# Volume_Button_LED_5.net
KiCad netlist of a schematic drawn in EAGLE
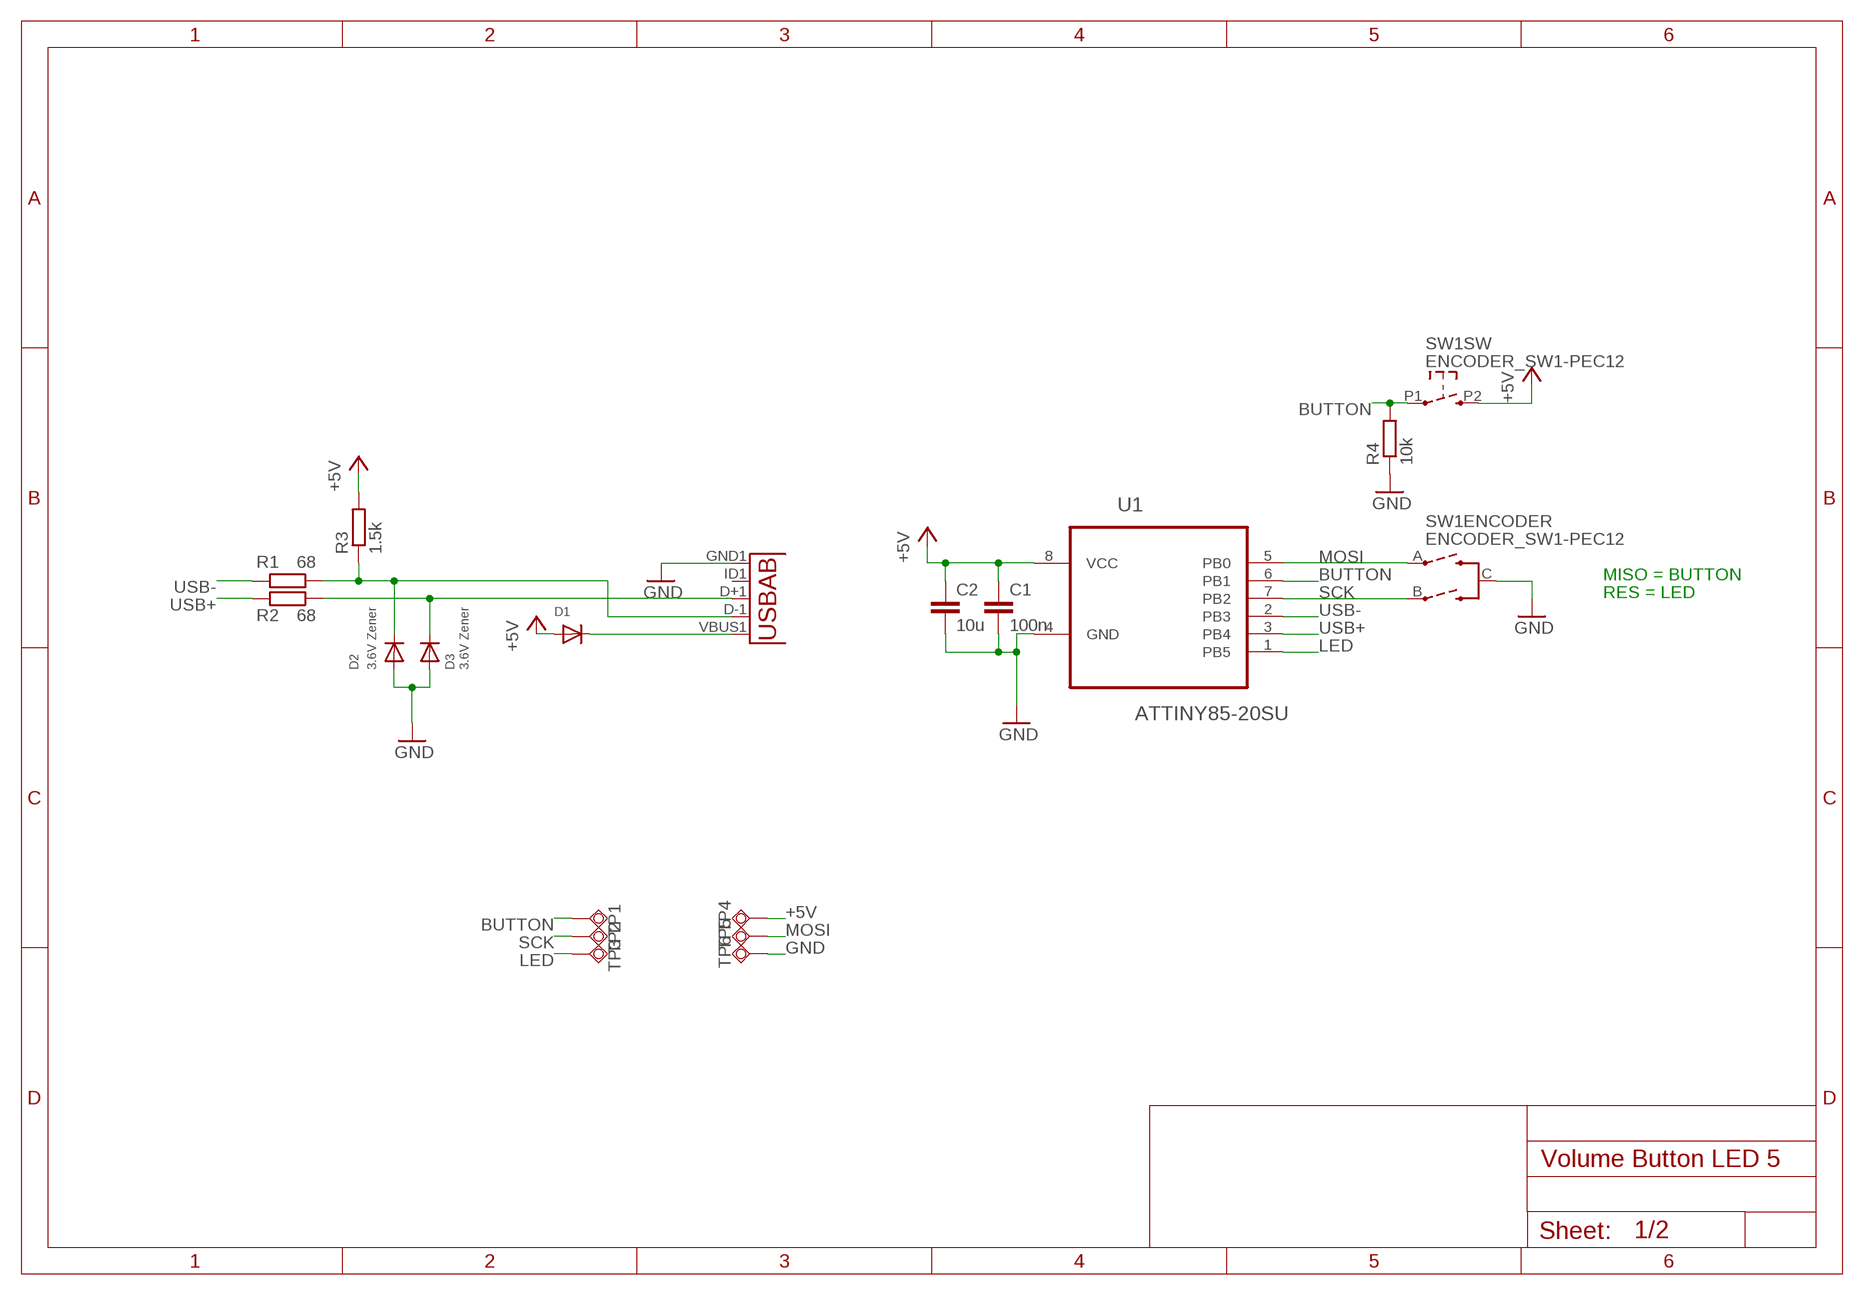
[diagram p0: schematic, sheet 1]
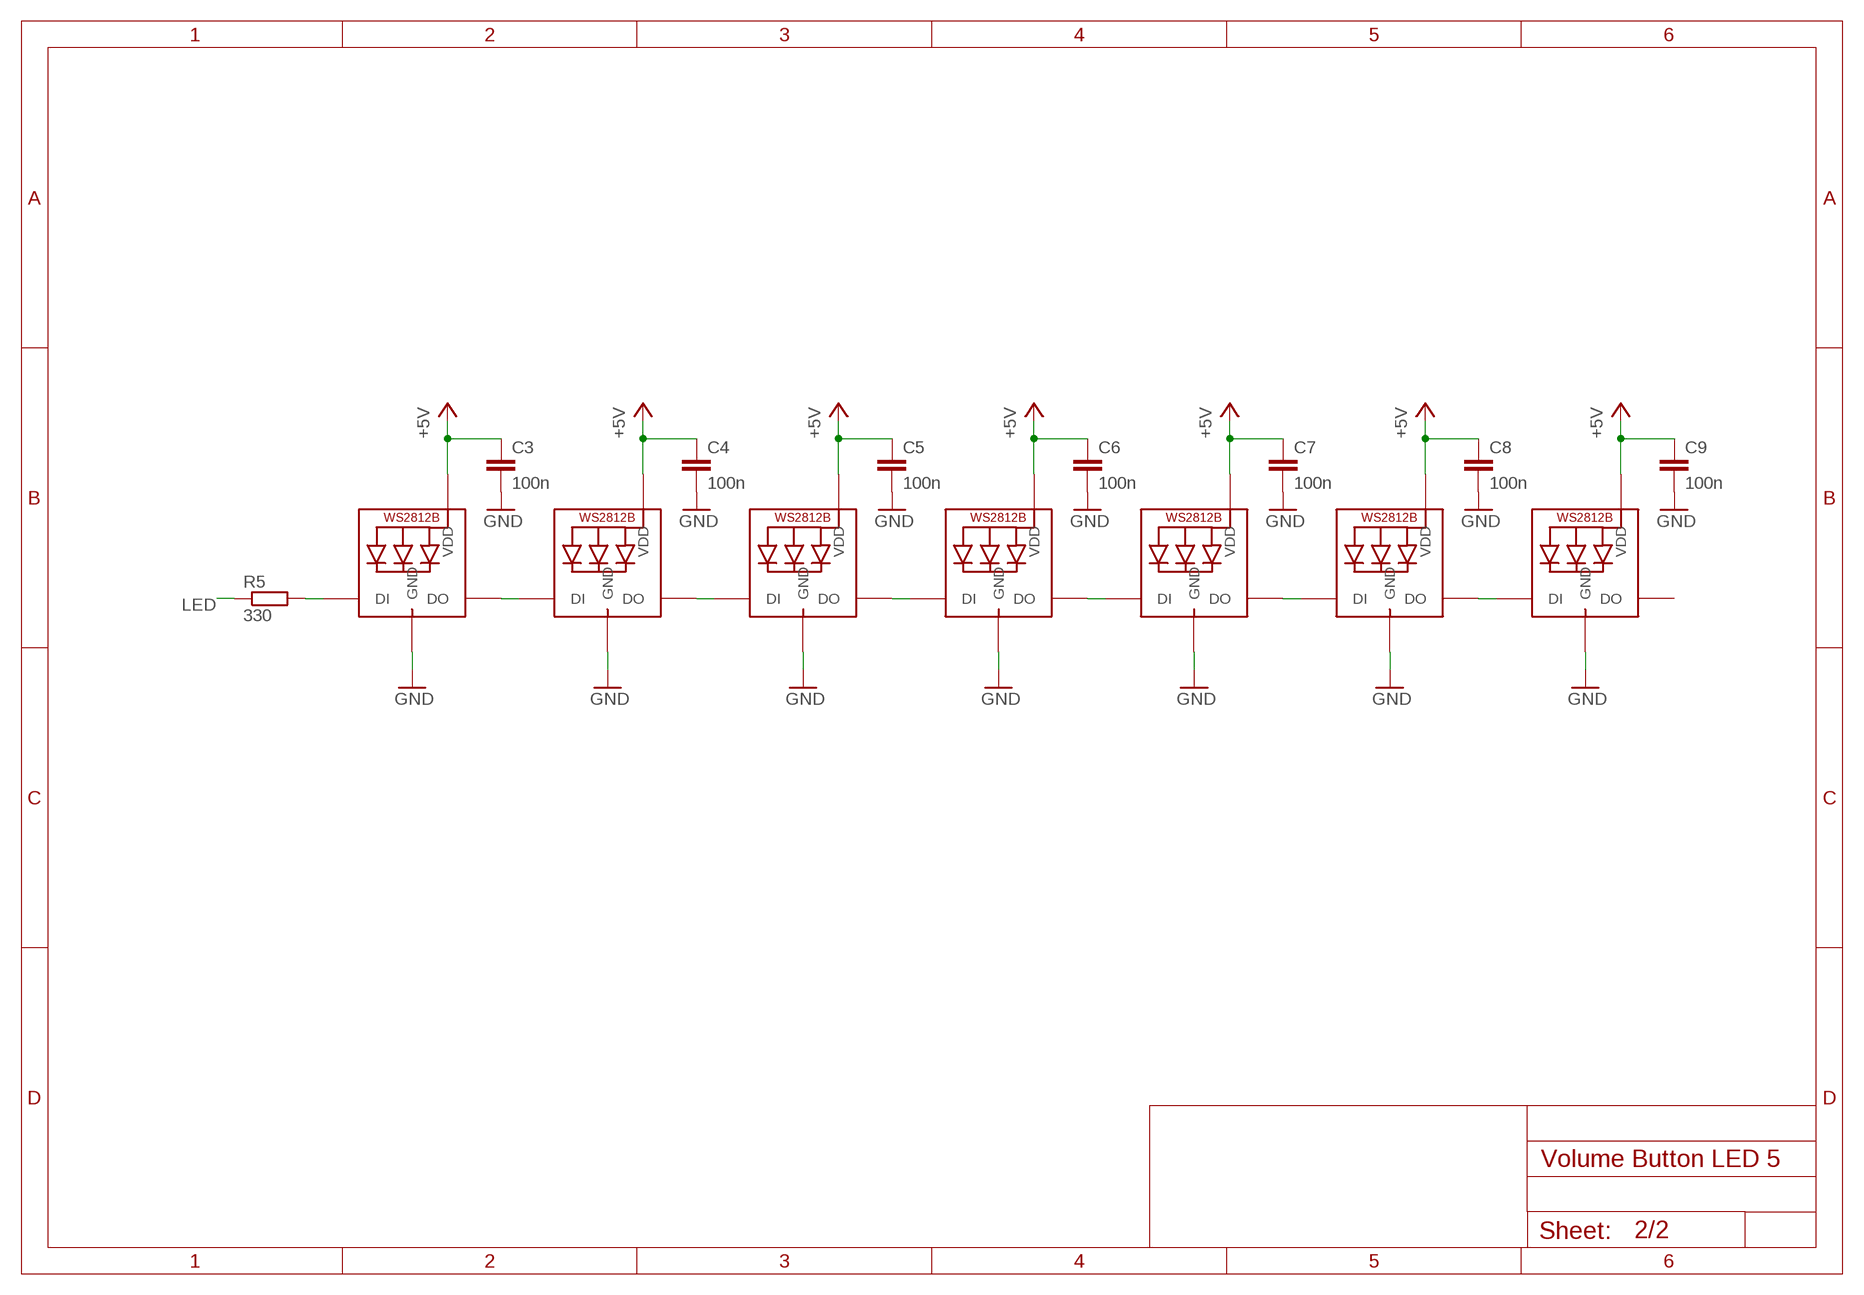
[diagram p1: schematic, sheet 2]

(export (version "E")
  (design (tool "Eeschema 10.0.6"))
  (components
    (comp (ref "C3")
      (value "100n")
      (footprint "eagle-import:C0805")
      (libsource (lib "eagle-import") (part "C-EUC0805"))
    )
    (comp (ref "C4")
      (value "100n")
      (footprint "eagle-import:C0805")
      (libsource (lib "eagle-import") (part "C-EUC0805"))
    )
    (comp (ref "C5")
      (value "100n")
      (footprint "eagle-import:C0805")
      (libsource (lib "eagle-import") (part "C-EUC0805"))
    )
    (comp (ref "C6")
      (value "100n")
      (footprint "eagle-import:C0805")
      (libsource (lib "eagle-import") (part "C-EUC0805"))
    )
    (comp (ref "C7")
      (value "100n")
      (footprint "eagle-import:C0805")
      (libsource (lib "eagle-import") (part "C-EUC0805"))
    )
    (comp (ref "C8")
      (value "100n")
      (footprint "eagle-import:C0805")
      (libsource (lib "eagle-import") (part "C-EUC0805"))
    )
    (comp (ref "C9")
      (value "100n")
      (footprint "eagle-import:C0805")
      (libsource (lib "eagle-import") (part "C-EUC0805"))
    )
    (comp (ref "LED1")
      (value "WS2812B5050")
      (footprint "eagle-import:WS2812B")
      (libsource (lib "eagle-import") (part "WS2812B5050"))
    )
    (comp (ref "LED2")
      (value "WS2812B5050")
      (footprint "eagle-import:WS2812B")
      (libsource (lib "eagle-import") (part "WS2812B5050"))
    )
    (comp (ref "LED3")
      (value "WS2812B5050")
      (footprint "eagle-import:WS2812B")
      (libsource (lib "eagle-import") (part "WS2812B5050"))
    )
    (comp (ref "LED4")
      (value "WS2812B5050")
      (footprint "eagle-import:WS2812B")
      (libsource (lib "eagle-import") (part "WS2812B5050"))
    )
    (comp (ref "LED5")
      (value "WS2812B5050")
      (footprint "eagle-import:WS2812B")
      (libsource (lib "eagle-import") (part "WS2812B5050"))
    )
    (comp (ref "LED6")
      (value "WS2812B5050")
      (footprint "eagle-import:WS2812B")
      (libsource (lib "eagle-import") (part "WS2812B5050"))
    )
    (comp (ref "LED7")
      (value "WS2812B5050")
      (footprint "eagle-import:WS2812B")
      (libsource (lib "eagle-import") (part "WS2812B5050"))
    )
    (comp (ref "R5")
      (value "330")
      (footprint "eagle-import:R0805")
      (libsource (lib "eagle-import") (part "R-EU_R0805"))
    )
    (comp (ref "C1")
      (value "100n")
      (footprint "eagle-import:C0805")
      (libsource (lib "eagle-import") (part "C-EUC0805"))
    )
    (comp (ref "C2")
      (value "10u")
      (footprint "eagle-import:C0805")
      (libsource (lib "eagle-import") (part "C-EUC0805"))
    )
    (comp (ref "D1")
      (value "DIODESOD-123")
      (footprint "eagle-import:SOD-123")
      (libsource (lib "eagle-import") (part "DIODESOD-123"))
    )
    (comp (ref "D2")
      (value "3.6V Zener")
      (footprint "eagle-import:SOD-323F")
      (libsource (lib "eagle-import") (part "DIODESOD-323F"))
    )
    (comp (ref "D3")
      (value "3.6V Zener")
      (footprint "eagle-import:SOD-323F")
      (libsource (lib "eagle-import") (part "DIODESOD-323F"))
    )
    (comp (ref "R1")
      (value "68")
      (footprint "eagle-import:R0603")
      (libsource (lib "eagle-import") (part "R-EU_R0603"))
    )
    (comp (ref "R2")
      (value "68")
      (footprint "eagle-import:R0603")
      (libsource (lib "eagle-import") (part "R-EU_R0603"))
    )
    (comp (ref "R3")
      (value "1.5k")
      (footprint "eagle-import:R0603")
      (libsource (lib "eagle-import") (part "R-EU_R0603"))
    )
    (comp (ref "R4")
      (value "10k")
      (footprint "eagle-import:R0805")
      (libsource (lib "eagle-import") (part "R-EU_R0805"))
    )
    (comp (ref "SW1")
      (value "ENCODER_SW1-PEC12")
      (footprint "eagle-import:PEC12_INCREMENTAL_ENCODER")
      (libsource (lib "eagle-import") (part "ENCODER_SW1-PEC12"))
    )
    (comp (ref "TP1")
      (value "TPSQTP15R")
      (footprint "eagle-import:TP15R")
      (libsource (lib "eagle-import") (part "TPSQTP15R"))
    )
    (comp (ref "TP2")
      (value "TPSQTP15R")
      (footprint "eagle-import:TP15R")
      (libsource (lib "eagle-import") (part "TPSQTP15R"))
    )
    (comp (ref "TP3")
      (value "TPSQTP15R")
      (footprint "eagle-import:TP15R")
      (libsource (lib "eagle-import") (part "TPSQTP15R"))
    )
    (comp (ref "TP4")
      (value "TPSQTP15R")
      (footprint "eagle-import:TP15R")
      (libsource (lib "eagle-import") (part "TPSQTP15R"))
    )
    (comp (ref "TP5")
      (value "TPSQTP15R")
      (footprint "eagle-import:TP15R")
      (libsource (lib "eagle-import") (part "TPSQTP15R"))
    )
    (comp (ref "TP6")
      (value "TPSQTP15R")
      (footprint "eagle-import:TP15R")
      (libsource (lib "eagle-import") (part "TPSQTP15R"))
    )
    (comp (ref "U1")
      (value "ATTINY85-20SU")
      (footprint "eagle-import:SOIC127P798X216-8N")
      (libsource (lib "eagle-import") (part "ATTINY85-20SU"))
    )
    (comp (ref "U2")
      (value "USB\"\"")
      (footprint "eagle-import:USB-MICRO-SMD")
      (libsource (lib "eagle-import") (part "USB{dblquote}{dblquote}"))
    )
  )
  (nets
    (net (code "1") (name "+5V") (class "Default")
      (node (ref "C1") (pin "1") (pinfunction "1_1") (pintype "passive"))
      (node (ref "C2") (pin "1") (pinfunction "1_1") (pintype "passive"))
      (node (ref "C3") (pin "1") (pinfunction "1_1") (pintype "passive"))
      (node (ref "C4") (pin "1") (pinfunction "1_1") (pintype "passive"))
      (node (ref "C5") (pin "1") (pinfunction "1_1") (pintype "passive"))
      (node (ref "C6") (pin "1") (pinfunction "1_1") (pintype "passive"))
      (node (ref "C7") (pin "1") (pinfunction "1_1") (pintype "passive"))
      (node (ref "C8") (pin "1") (pinfunction "1_1") (pintype "passive"))
      (node (ref "C9") (pin "1") (pinfunction "1_1") (pintype "passive"))
      (node (ref "D1") (pin "A") (pinfunction "A_A") (pintype "passive"))
      (node (ref "LED1") (pin "1-VDD") (pinfunction "VDD_1-VDD") (pintype "power_in"))
      (node (ref "LED2") (pin "1-VDD") (pinfunction "VDD_1-VDD") (pintype "power_in"))
      (node (ref "LED3") (pin "1-VDD") (pinfunction "VDD_1-VDD") (pintype "power_in"))
      (node (ref "LED4") (pin "1-VDD") (pinfunction "VDD_1-VDD") (pintype "power_in"))
      (node (ref "LED5") (pin "1-VDD") (pinfunction "VDD_1-VDD") (pintype "power_in"))
      (node (ref "LED6") (pin "1-VDD") (pinfunction "VDD_1-VDD") (pintype "power_in"))
      (node (ref "LED7") (pin "1-VDD") (pinfunction "VDD_1-VDD") (pintype "power_in"))
      (node (ref "R3") (pin "2") (pinfunction "2_2") (pintype "passive"))
      (node (ref "SW1") (pin "P2") (pinfunction "2_P2") (pintype "passive"))
      (node (ref "TP4") (pin "TP") (pinfunction "TP_TP") (pintype "input"))
      (node (ref "U1") (pin "8") (pinfunction "VCC_8") (pintype "power_in"))
    )
    (net (code "2") (name "BUTTON") (class "Default")
      (node (ref "R4") (pin "2") (pinfunction "2_2") (pintype "passive"))
      (node (ref "SW1") (pin "P1") (pinfunction "1_P1") (pintype "passive"))
      (node (ref "TP1") (pin "TP") (pinfunction "TP_TP") (pintype "input"))
      (node (ref "U1") (pin "6") (pinfunction "PB1_6") (pintype "bidirectional"))
    )
    (net (code "3") (name "GND") (class "Default")
      (node (ref "C1") (pin "2") (pinfunction "2_2") (pintype "passive"))
      (node (ref "C2") (pin "2") (pinfunction "2_2") (pintype "passive"))
      (node (ref "C3") (pin "2") (pinfunction "2_2") (pintype "passive"))
      (node (ref "C4") (pin "2") (pinfunction "2_2") (pintype "passive"))
      (node (ref "C5") (pin "2") (pinfunction "2_2") (pintype "passive"))
      (node (ref "C6") (pin "2") (pinfunction "2_2") (pintype "passive"))
      (node (ref "C7") (pin "2") (pinfunction "2_2") (pintype "passive"))
      (node (ref "C8") (pin "2") (pinfunction "2_2") (pintype "passive"))
      (node (ref "C9") (pin "2") (pinfunction "2_2") (pintype "passive"))
      (node (ref "D2") (pin "A") (pinfunction "A_A") (pintype "passive"))
      (node (ref "D3") (pin "A") (pinfunction "A_A") (pintype "passive"))
      (node (ref "LED1") (pin "3-GND") (pinfunction "GND_3-GND") (pintype "power_in"))
      (node (ref "LED2") (pin "3-GND") (pinfunction "GND_3-GND") (pintype "power_in"))
      (node (ref "LED3") (pin "3-GND") (pinfunction "GND_3-GND") (pintype "power_in"))
      (node (ref "LED4") (pin "3-GND") (pinfunction "GND_3-GND") (pintype "power_in"))
      (node (ref "LED5") (pin "3-GND") (pinfunction "GND_3-GND") (pintype "power_in"))
      (node (ref "LED6") (pin "3-GND") (pinfunction "GND_3-GND") (pintype "power_in"))
      (node (ref "LED7") (pin "3-GND") (pinfunction "GND_3-GND") (pintype "power_in"))
      (node (ref "R4") (pin "1") (pinfunction "1_1") (pintype "passive"))
      (node (ref "SW1") (pin "C") (pinfunction "C_C") (pintype "passive"))
      (node (ref "TP6") (pin "TP") (pinfunction "TP_TP") (pintype "input"))
      (node (ref "U1") (pin "4") (pinfunction "GND_4") (pintype "passive"))
      (node (ref "U2") (pin "GND1") (pinfunction "GND_GND1") (pintype "bidirectional"))
    )
    (net (code "4") (name "LED") (class "Default")
      (node (ref "R5") (pin "1") (pinfunction "1_1") (pintype "passive"))
      (node (ref "TP3") (pin "TP") (pinfunction "TP_TP") (pintype "input"))
      (node (ref "U1") (pin "1") (pinfunction "PB5_1") (pintype "bidirectional"))
    )
    (net (code "5") (name "MOSI") (class "Default")
      (node (ref "SW1") (pin "A") (pinfunction "A_A") (pintype "passive"))
      (node (ref "TP5") (pin "TP") (pinfunction "TP_TP") (pintype "input"))
      (node (ref "U1") (pin "5") (pinfunction "PB0_5") (pintype "bidirectional"))
    )
    (net (code "6") (name "Net-(LED1-DI)") (class "Default")
      (node (ref "LED1") (pin "4-DIN") (pinfunction "DI_4-DIN") (pintype "input"))
      (node (ref "R5") (pin "2") (pinfunction "2_2") (pintype "passive"))
    )
    (net (code "7") (name "Net-(LED1-DO)") (class "Default")
      (node (ref "LED1") (pin "2-DOUT") (pinfunction "DO_2-DOUT") (pintype "output"))
      (node (ref "LED2") (pin "4-DIN") (pinfunction "DI_4-DIN") (pintype "input"))
    )
    (net (code "8") (name "Net-(LED2-DO)") (class "Default")
      (node (ref "LED2") (pin "2-DOUT") (pinfunction "DO_2-DOUT") (pintype "output"))
      (node (ref "LED3") (pin "4-DIN") (pinfunction "DI_4-DIN") (pintype "input"))
    )
    (net (code "9") (name "Net-(LED3-DO)") (class "Default")
      (node (ref "LED3") (pin "2-DOUT") (pinfunction "DO_2-DOUT") (pintype "output"))
      (node (ref "LED4") (pin "4-DIN") (pinfunction "DI_4-DIN") (pintype "input"))
    )
    (net (code "10") (name "Net-(LED4-DO)") (class "Default")
      (node (ref "LED4") (pin "2-DOUT") (pinfunction "DO_2-DOUT") (pintype "output"))
      (node (ref "LED5") (pin "4-DIN") (pinfunction "DI_4-DIN") (pintype "input"))
    )
    (net (code "11") (name "Net-(LED5-DO)") (class "Default")
      (node (ref "LED5") (pin "2-DOUT") (pinfunction "DO_2-DOUT") (pintype "output"))
      (node (ref "LED6") (pin "4-DIN") (pinfunction "DI_4-DIN") (pintype "input"))
    )
    (net (code "12") (name "Net-(LED6-DO)") (class "Default")
      (node (ref "LED6") (pin "2-DOUT") (pinfunction "DO_2-DOUT") (pintype "output"))
      (node (ref "LED7") (pin "4-DIN") (pinfunction "DI_4-DIN") (pintype "input"))
    )
    (net (code "13") (name "Net-(U2-D+)") (class "Default")
      (node (ref "D3") (pin "C") (pinfunction "C_C") (pintype "passive"))
      (node (ref "R2") (pin "1") (pinfunction "1_1") (pintype "passive"))
      (node (ref "U2") (pin "D+1") (pinfunction "D+_D+1") (pintype "bidirectional"))
    )
    (net (code "14") (name "Net-(U2-D-)") (class "Default")
      (node (ref "D2") (pin "C") (pinfunction "C_C") (pintype "passive"))
      (node (ref "R1") (pin "1") (pinfunction "1_1") (pintype "passive"))
      (node (ref "R3") (pin "1") (pinfunction "1_1") (pintype "passive"))
      (node (ref "U2") (pin "D-1") (pinfunction "D-_D-1") (pintype "bidirectional"))
    )
    (net (code "15") (name "Net-(U2-VBUS)") (class "Default")
      (node (ref "D1") (pin "C") (pinfunction "C_C") (pintype "passive"))
      (node (ref "U2") (pin "VBUS1") (pinfunction "VBUS_VBUS1") (pintype "bidirectional"))
    )
    (net (code "16") (name "SCK") (class "Default")
      (node (ref "SW1") (pin "B") (pinfunction "B_B") (pintype "passive"))
      (node (ref "TP2") (pin "TP") (pinfunction "TP_TP") (pintype "input"))
      (node (ref "U1") (pin "7") (pinfunction "PB2_7") (pintype "bidirectional"))
    )
    (net (code "17") (name "USB+") (class "Default")
      (node (ref "R2") (pin "2") (pinfunction "2_2") (pintype "passive"))
      (node (ref "U1") (pin "3") (pinfunction "PB4_3") (pintype "bidirectional"))
    )
    (net (code "18") (name "USB-") (class "Default")
      (node (ref "R1") (pin "2") (pinfunction "2_2") (pintype "passive"))
      (node (ref "U1") (pin "2") (pinfunction "PB3_2") (pintype "bidirectional"))
    )
    (net (code "19") (name "unconnected-(LED7-DO-Pad2-DOUT)") (class "Default")
      (node (ref "LED7") (pin "2-DOUT") (pinfunction "DO_2-DOUT") (pintype "output"))
    )
    (net (code "20") (name "unconnected-(U2-USBID-PadID1)") (class "Default")
      (node (ref "U2") (pin "ID1") (pinfunction "USBID_ID1") (pintype "bidirectional"))
    )
  )
)
